# 02_FPGA_Bank0.net
KiCad netlist of a schematic drawn in Altium Designer
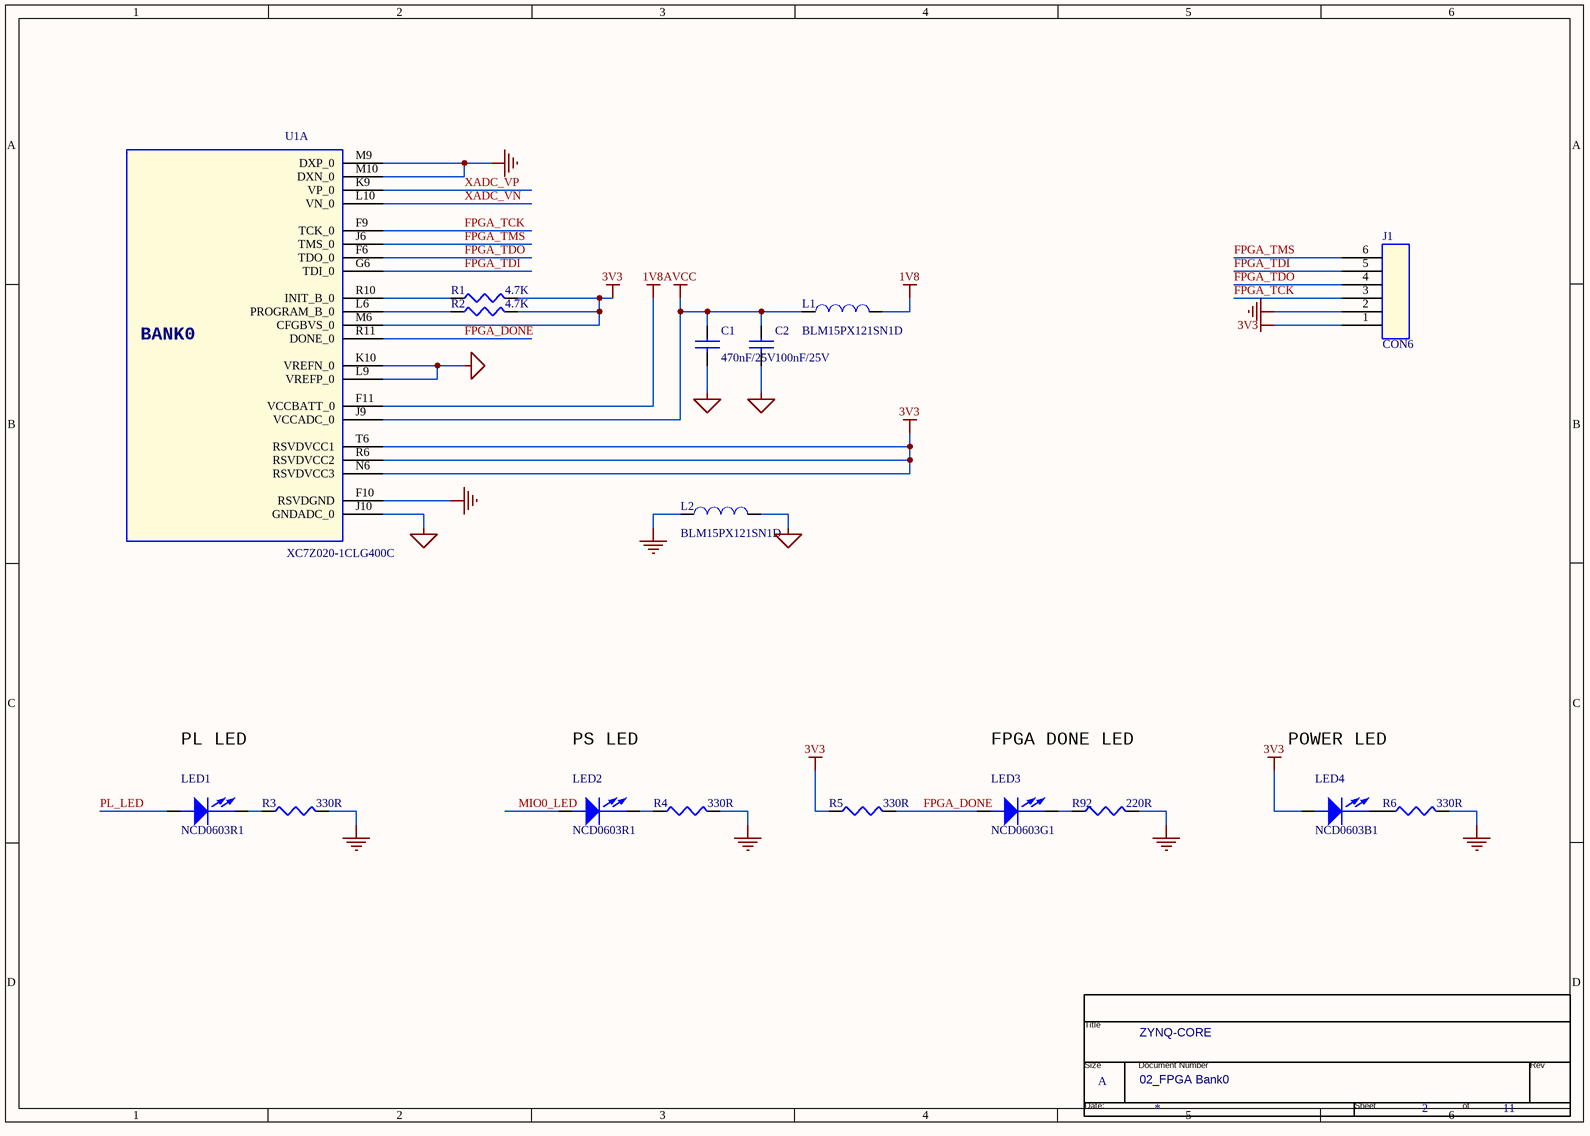
[diagram p0: 02_FPGA Bank0.SchDoc]

(export (version "E")
  (design (tool "Eeschema 10.0.6"))
  (components
    (comp (ref "C1") (value "470nF/25V") (footprint "C0402") (libsource (lib "*") (part "CAP NP_Dup1")))
    (comp (ref "C2") (value "100nF/25V") (footprint "C0402") (libsource (lib "*") (part "CAP NP_Dup1")))
    (comp (ref "J1") (value "CON6") (footprint "HDR1X6") (libsource (lib "*") (part "CON6")))
    (comp (ref "L1")
      (value "BLM15PX121SN1D")
      (footprint "L0402")
      (libsource (lib "*") (part "INDUCTOR_Dup1"))
    )
    (comp (ref "L2")
      (value "BLM15PX121SN1D")
      (footprint "L0402")
      (libsource (lib "*") (part "INDUCTOR_Dup1"))
    )
    (comp (ref "LED1")
      (value "NCD0603R1")
      (footprint "LED0603_M_RED")
      (description "红色")
      (libsource (lib "*") (part "LED"))
    )
    (comp (ref "LED2")
      (value "NCD0603R1")
      (footprint "LED0603_M_RED")
      (description "红色")
      (libsource (lib "*") (part "LED"))
    )
    (comp (ref "LED3")
      (value "NCD0603G1")
      (footprint "LED0603_M_GREEN")
      (description "绿色")
      (libsource (lib "*") (part "LED"))
    )
    (comp (ref "LED4")
      (value "NCD0603B1")
      (footprint "LED0603_M_BLUE")
      (description "蓝色")
      (libsource (lib "*") (part "LED"))
    )
    (comp (ref "R1") (value "4.7K") (footprint "R0402A") (libsource (lib "*") (part "RESISTOR_Dup1")))
    (comp (ref "R2") (value "4.7K") (footprint "R0402A") (libsource (lib "*") (part "RESISTOR_Dup1")))
    (comp (ref "R3") (value "330R") (footprint "R0402") (libsource (lib "*") (part "RESISTOR_Dup1")))
    (comp (ref "R4") (value "330R") (footprint "R0402") (libsource (lib "*") (part "RESISTOR_Dup1")))
    (comp (ref "R5") (value "330R") (footprint "R0402") (libsource (lib "*") (part "RESISTOR_Dup1")))
    (comp (ref "R6") (value "330R") (footprint "R0402") (libsource (lib "*") (part "RESISTOR_Dup1")))
    (comp (ref "R92") (value "220R") (footprint "R0402") (libsource (lib "*") (part "RESISTOR_Dup1")))
    (comp (ref "U1")
      (value "XC7Z020-1CLG400C")
      (footprint "CLG400")
      (libsource (lib "*") (part "Zynq7010/7020"))
    )
  )
  (nets
    (net (code "1") (name "/FPGA_DONE") (class "Default")
      (node (ref "LED3") (pin "1") (pinfunction "ANODE_1") (pintype "passive"))
      (node (ref "R5") (pin "2") (pinfunction "2_2") (pintype "passive"))
      (node (ref "U1") (pin "R11") (pinfunction "DONE_0_R11") (pintype "passive"))
    )
    (net (code "2") (name "/FPGA_TCK") (class "Default")
      (node (ref "J1") (pin "3") (pinfunction "3_3") (pintype "passive"))
      (node (ref "U1") (pin "F9") (pinfunction "TCK_0_F9") (pintype "passive"))
    )
    (net (code "3") (name "/FPGA_TDI") (class "Default")
      (node (ref "J1") (pin "5") (pinfunction "5_5") (pintype "passive"))
      (node (ref "U1") (pin "G6") (pinfunction "TDI_0_G6") (pintype "passive"))
    )
    (net (code "4") (name "/FPGA_TDO") (class "Default")
      (node (ref "J1") (pin "4") (pinfunction "4_4") (pintype "passive"))
      (node (ref "U1") (pin "F6") (pinfunction "TDO_0_F6") (pintype "passive"))
    )
    (net (code "5") (name "/FPGA_TMS") (class "Default")
      (node (ref "J1") (pin "6") (pinfunction "6_6") (pintype "passive"))
      (node (ref "U1") (pin "J6") (pinfunction "TMS_0_J6") (pintype "passive"))
    )
    (net (code "6") (name "/MIO0_LED") (class "Default")
      (node (ref "LED2") (pin "1") (pinfunction "ANODE_1") (pintype "passive"))
    )
    (net (code "7") (name "/PL_LED") (class "Default")
      (node (ref "LED1") (pin "1") (pinfunction "ANODE_1") (pintype "passive"))
    )
    (net (code "8") (name "/XADC_VN") (class "Default")
      (node (ref "U1") (pin "L10") (pinfunction "VN_0_L10") (pintype "passive"))
    )
    (net (code "9") (name "/XADC_VP") (class "Default")
      (node (ref "U1") (pin "K9") (pinfunction "VP_0_K9") (pintype "passive"))
    )
    (net (code "10") (name "1V8") (class "Default")
      (node (ref "L1") (pin "2") (pinfunction "2_2") (pintype "passive"))
      (node (ref "U1") (pin "F11") (pinfunction "VCCBATT_0_F11") (pintype "passive"))
    )
    (net (code "11") (name "3V3") (class "Default")
      (node (ref "J1") (pin "1") (pinfunction "1_1") (pintype "passive"))
      (node (ref "LED4") (pin "1") (pinfunction "ANODE_1") (pintype "passive"))
      (node (ref "R1") (pin "2") (pinfunction "2_2") (pintype "passive"))
      (node (ref "R2") (pin "2") (pinfunction "2_2") (pintype "passive"))
      (node (ref "R5") (pin "1") (pinfunction "1_1") (pintype "passive"))
      (node (ref "U1") (pin "M6") (pinfunction "CFGBVS_0_M6") (pintype "passive"))
      (node (ref "U1") (pin "N6") (pinfunction "RSVDVCC3_N6") (pintype "passive"))
      (node (ref "U1") (pin "R6") (pinfunction "RSVDVCC2_R6") (pintype "passive"))
      (node (ref "U1") (pin "T6") (pinfunction "RSVDVCC1_T6") (pintype "passive"))
    )
    (net (code "12") (name "AGND") (class "Default")
      (node (ref "C1") (pin "2") (pinfunction "2_2") (pintype "passive"))
      (node (ref "C2") (pin "2") (pinfunction "2_2") (pintype "passive"))
      (node (ref "L2") (pin "2") (pinfunction "2_2") (pintype "passive"))
      (node (ref "U1") (pin "J10") (pinfunction "GNDADC_0_J10") (pintype "passive"))
      (node (ref "U1") (pin "K10") (pinfunction "VREFN_0_K10") (pintype "passive"))
      (node (ref "U1") (pin "L9") (pinfunction "VREFP_0_L9") (pintype "passive"))
    )
    (net (code "13") (name "AVCC") (class "Default")
      (node (ref "C1") (pin "1") (pinfunction "1_1") (pintype "passive"))
      (node (ref "C2") (pin "1") (pinfunction "1_1") (pintype "passive"))
      (node (ref "L1") (pin "1") (pinfunction "1_1") (pintype "passive"))
      (node (ref "U1") (pin "J9") (pinfunction "VCCADC_0_J9") (pintype "passive"))
    )
    (net (code "14") (name "GND") (class "Default")
      (node (ref "J1") (pin "2") (pinfunction "2_2") (pintype "passive"))
      (node (ref "L2") (pin "1") (pinfunction "1_1") (pintype "passive"))
      (node (ref "R3") (pin "2") (pinfunction "2_2") (pintype "passive"))
      (node (ref "R4") (pin "2") (pinfunction "2_2") (pintype "passive"))
      (node (ref "R6") (pin "2") (pinfunction "2_2") (pintype "passive"))
      (node (ref "R92") (pin "2") (pinfunction "2_2") (pintype "passive"))
      (node (ref "U1") (pin "F10") (pinfunction "RSVDGND_F10") (pintype "passive"))
      (node (ref "U1") (pin "M10") (pinfunction "DXN_0_M10") (pintype "passive"))
      (node (ref "U1") (pin "M9") (pinfunction "DXP_0_M9") (pintype "passive"))
    )
    (net (code "15") (name "Net-(LED1-CATHODE)") (class "Default")
      (node (ref "LED1") (pin "2") (pinfunction "CATHODE_2") (pintype "passive"))
      (node (ref "R3") (pin "1") (pinfunction "1_1") (pintype "passive"))
    )
    (net (code "16") (name "Net-(LED2-CATHODE)") (class "Default")
      (node (ref "LED2") (pin "2") (pinfunction "CATHODE_2") (pintype "passive"))
      (node (ref "R4") (pin "1") (pinfunction "1_1") (pintype "passive"))
    )
    (net (code "17") (name "Net-(LED3-CATHODE)") (class "Default")
      (node (ref "LED3") (pin "2") (pinfunction "CATHODE_2") (pintype "passive"))
      (node (ref "R92") (pin "1") (pinfunction "1_1") (pintype "passive"))
    )
    (net (code "18") (name "Net-(LED4-CATHODE)") (class "Default")
      (node (ref "LED4") (pin "2") (pinfunction "CATHODE_2") (pintype "passive"))
      (node (ref "R6") (pin "1") (pinfunction "1_1") (pintype "passive"))
    )
    (net (code "19") (name "Net-(U1A-INIT_B_0)") (class "Default")
      (node (ref "R1") (pin "1") (pinfunction "1_1") (pintype "passive"))
      (node (ref "U1") (pin "R10") (pinfunction "INIT_B_0_R10") (pintype "passive"))
    )
    (net (code "20") (name "Net-(U1A-PROGRAM_B_0)") (class "Default")
      (node (ref "R2") (pin "1") (pinfunction "1_1") (pintype "passive"))
      (node (ref "U1") (pin "L6") (pinfunction "PROGRAM_B_0_L6") (pintype "passive"))
    )
  )
)
